# Adafruit_CH334F_Mini_4-Port_USB_Hub_Brea.net
KiCad netlist of a schematic drawn in EAGLE
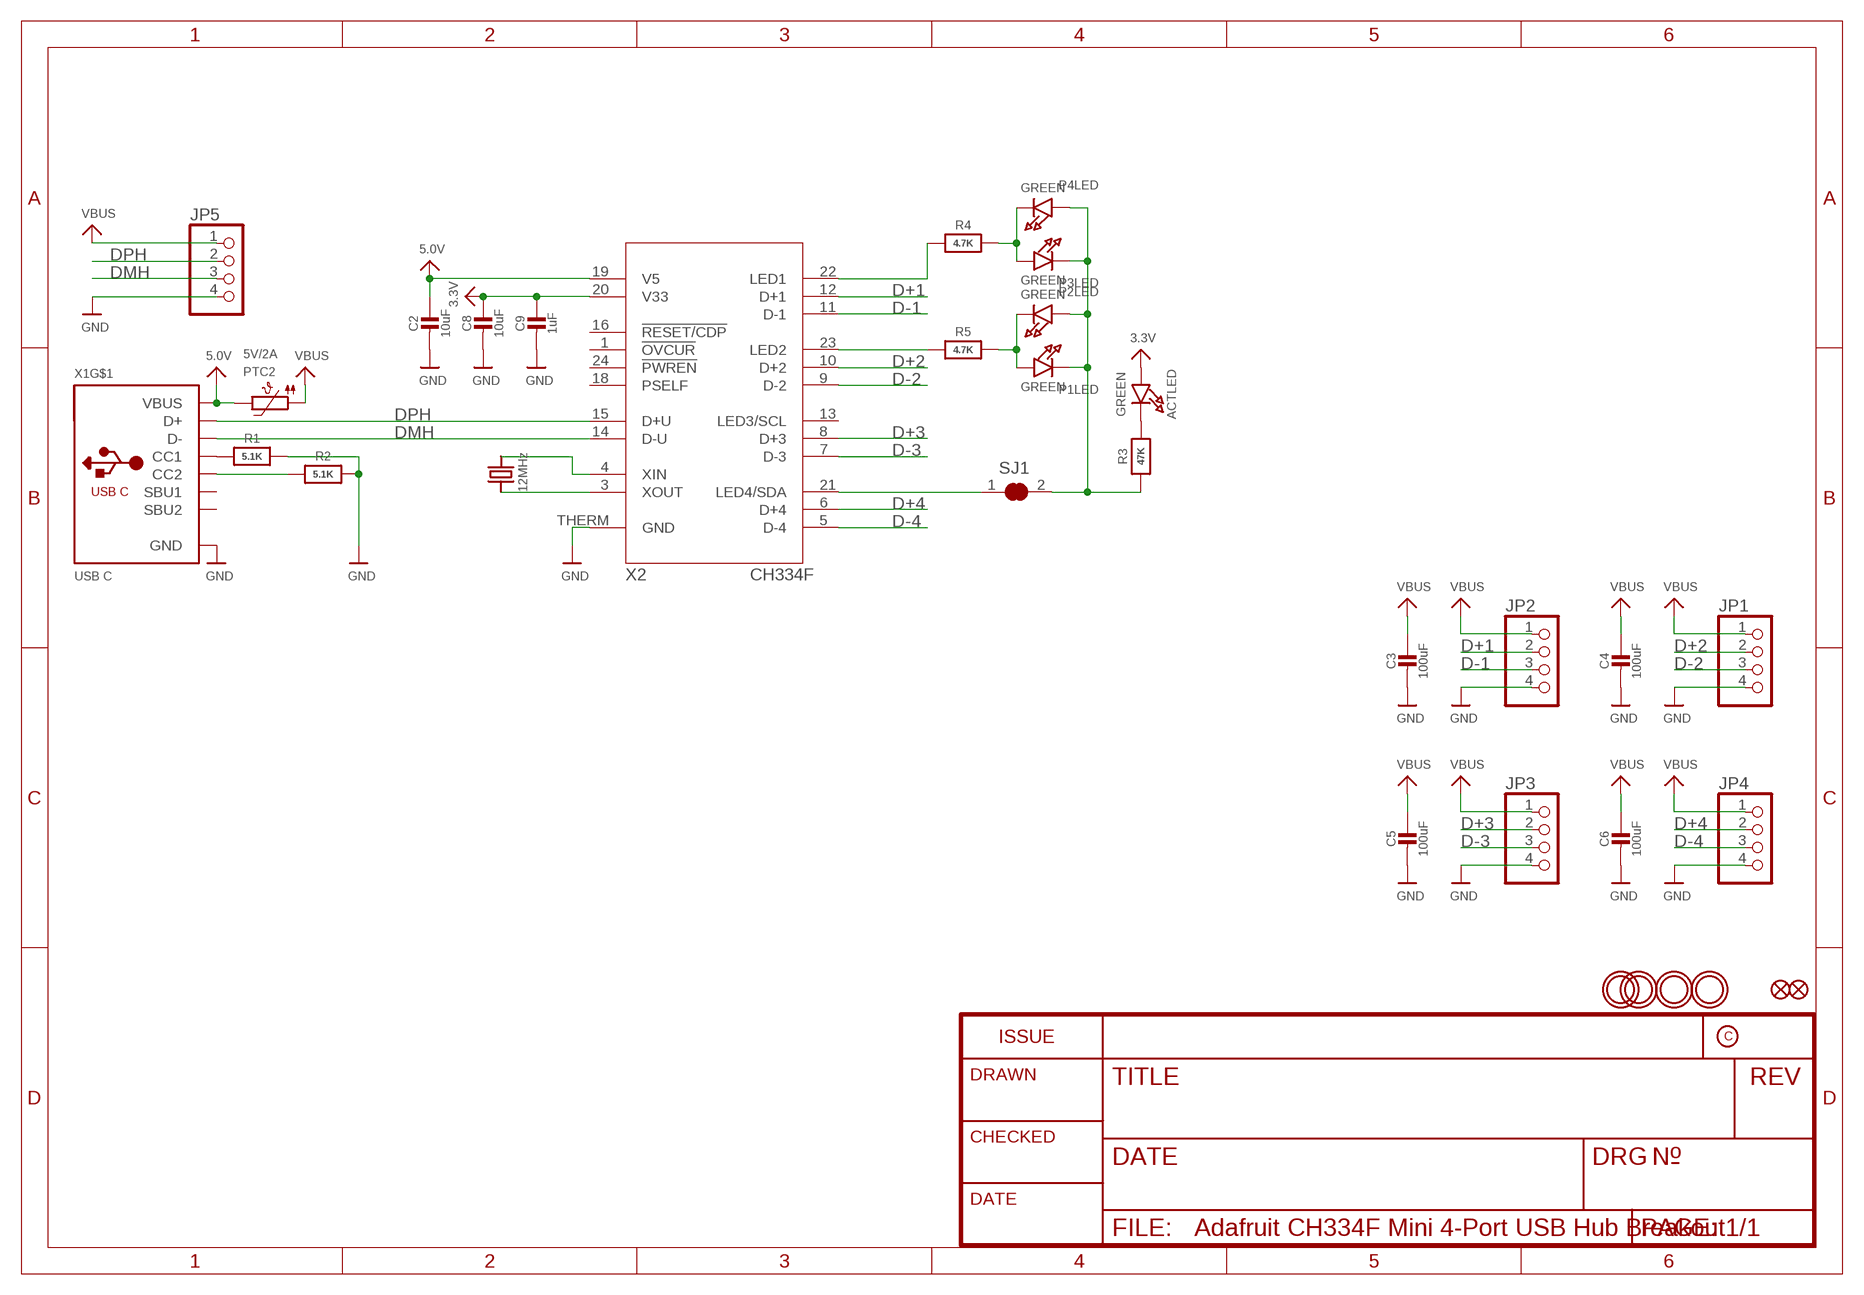
[diagram p0: schematic, sheet 1]

(export (version "E")
  (design (tool "Eeschema 10.0.6"))
  (components
    (comp (ref "ACTLED")
      (value "GREEN")
      (footprint "eagle-import:CHIPLED_0603_NOOUTLINE")
      (libsource (lib "eagle-import") (part "LED0603_NOOUTLINE"))
    )
    (comp (ref "C2")
      (value "10uF")
      (footprint "eagle-import:0805-NO")
      (libsource (lib "eagle-import") (part "CAP_CERAMIC0805-NOOUTLINE"))
    )
    (comp (ref "C3")
      (value "100uF")
      (footprint "eagle-import:_1206")
      (libsource (lib "eagle-import") (part "CAP_CERAMIC_1206"))
    )
    (comp (ref "C4")
      (value "100uF")
      (footprint "eagle-import:_1206")
      (libsource (lib "eagle-import") (part "CAP_CERAMIC_1206"))
    )
    (comp (ref "C5")
      (value "100uF")
      (footprint "eagle-import:_1206")
      (libsource (lib "eagle-import") (part "CAP_CERAMIC_1206"))
    )
    (comp (ref "C6")
      (value "100uF")
      (footprint "eagle-import:_1206")
      (libsource (lib "eagle-import") (part "CAP_CERAMIC_1206"))
    )
    (comp (ref "C8")
      (value "10uF")
      (footprint "eagle-import:0805-NO")
      (libsource (lib "eagle-import") (part "CAP_CERAMIC0805-NOOUTLINE"))
    )
    (comp (ref "C9")
      (value "1uF")
      (footprint "eagle-import:0603-NO")
      (libsource (lib "eagle-import") (part "CAP_CERAMIC0603_NO"))
    )
    (comp (ref "FID1")
      (value "FIDUCIAL_0.5MM")
      (footprint "eagle-import:FIDUCIAL_0.5MM")
      (libsource (lib "eagle-import") (part "FIDUCIAL_0.5MM"))
    )
    (comp (ref "FID2")
      (value "FIDUCIAL_0.5MM")
      (footprint "eagle-import:FIDUCIAL_0.5MM")
      (libsource (lib "eagle-import") (part "FIDUCIAL_0.5MM"))
    )
    (comp (ref "JP1")
      (value "HEADER-1X4ROUND")
      (footprint "eagle-import:1X04_ROUND")
      (libsource (lib "eagle-import") (part "HEADER-1X4ROUND"))
    )
    (comp (ref "JP2")
      (value "HEADER-1X4ROUND")
      (footprint "eagle-import:1X04_ROUND")
      (libsource (lib "eagle-import") (part "HEADER-1X4ROUND"))
    )
    (comp (ref "JP3")
      (value "HEADER-1X4ROUND")
      (footprint "eagle-import:1X04_ROUND")
      (libsource (lib "eagle-import") (part "HEADER-1X4ROUND"))
    )
    (comp (ref "JP4")
      (value "HEADER-1X4ROUND")
      (footprint "eagle-import:1X04_ROUND")
      (libsource (lib "eagle-import") (part "HEADER-1X4ROUND"))
    )
    (comp (ref "JP5")
      (value "HEADER-1X4ROUND")
      (footprint "eagle-import:1X04_ROUND")
      (libsource (lib "eagle-import") (part "HEADER-1X4ROUND"))
    )
    (comp (ref "P1LED")
      (value "GREEN")
      (footprint "eagle-import:CHIPLED_0603_NOOUTLINE")
      (libsource (lib "eagle-import") (part "LED0603_NOOUTLINE"))
    )
    (comp (ref "P2LED")
      (value "GREEN")
      (footprint "eagle-import:CHIPLED_0603_NOOUTLINE")
      (libsource (lib "eagle-import") (part "LED0603_NOOUTLINE"))
    )
    (comp (ref "P3LED")
      (value "GREEN")
      (footprint "eagle-import:CHIPLED_0603_NOOUTLINE")
      (libsource (lib "eagle-import") (part "LED0603_NOOUTLINE"))
    )
    (comp (ref "P4LED")
      (value "GREEN")
      (footprint "eagle-import:CHIPLED_0603_NOOUTLINE")
      (libsource (lib "eagle-import") (part "LED0603_NOOUTLINE"))
    )
    (comp (ref "PTC2")
      (value "5V/2A")
      (footprint "eagle-import:0805-NO")
      (libsource (lib "eagle-import") (part "PTC_0805"))
    )
    (comp (ref "R1")
      (value "5.1K")
      (footprint "eagle-import:0603-NO")
      (libsource (lib "eagle-import") (part "RESISTOR_0603_NOOUT"))
    )
    (comp (ref "R2")
      (value "5.1K")
      (footprint "eagle-import:0603-NO")
      (libsource (lib "eagle-import") (part "RESISTOR_0603_NOOUT"))
    )
    (comp (ref "R3")
      (value "47K")
      (footprint "eagle-import:0603-NO")
      (libsource (lib "eagle-import") (part "RESISTOR_0603_NOOUT"))
    )
    (comp (ref "R4")
      (value "4.7K")
      (footprint "eagle-import:0603-NO")
      (libsource (lib "eagle-import") (part "RESISTOR_0603_NOOUT"))
    )
    (comp (ref "R5")
      (value "4.7K")
      (footprint "eagle-import:0603-NO")
      (libsource (lib "eagle-import") (part "RESISTOR_0603_NOOUT"))
    )
    (comp (ref "SJ1")
      (value "SOLDERJUMPER_CLOSED")
      (footprint "eagle-import:SOLDERJUMPER_CLOSEDWIRE")
      (libsource (lib "eagle-import") (part "SOLDERJUMPER_CLOSED"))
    )
    (comp (ref "U$23")
      (value "MOUNTINGHOLE2.5")
      (footprint "eagle-import:MOUNTINGHOLE_2.5_PLATED")
      (libsource (lib "eagle-import") (part "MOUNTINGHOLE2.5"))
    )
    (comp (ref "U$28")
      (value "MOUNTINGHOLE2.5")
      (footprint "eagle-import:MOUNTINGHOLE_2.5_PLATED")
      (libsource (lib "eagle-import") (part "MOUNTINGHOLE2.5"))
    )
    (comp (ref "U$29")
      (value "MOUNTINGHOLE2.5")
      (footprint "eagle-import:MOUNTINGHOLE_2.5_PLATED")
      (libsource (lib "eagle-import") (part "MOUNTINGHOLE2.5"))
    )
    (comp (ref "U$31")
      (value "MOUNTINGHOLE2.5")
      (footprint "eagle-import:MOUNTINGHOLE_2.5_PLATED")
      (libsource (lib "eagle-import") (part "MOUNTINGHOLE2.5"))
    )
    (comp (ref "X1")
      (value "USB C")
      (footprint "eagle-import:USB_C_CUSB31-CFM2AX-01-X")
      (libsource (lib "eagle-import") (part "USB_C"))
    )
    (comp (ref "X2")
      (value "CH334F")
      (footprint "eagle-import:QFN24_4MM")
      (libsource (lib "eagle-import") (part "CH334F"))
    )
    (comp (ref "Y1")
      (value "12MHz")
      (footprint "eagle-import:CRYSTAL_2.5X2")
      (libsource (lib "eagle-import") (part "CRYSTAL2.5X2.0"))
    )
  )
  (nets
    (net (code "1") (name "/D+1") (class "Default")
      (node (ref "JP2") (pin "2") (pinfunction "2_2") (pintype "passive"))
      (node (ref "X2") (pin "12") (pinfunction "D+1_12") (pintype "bidirectional"))
    )
    (net (code "2") (name "/D+2") (class "Default")
      (node (ref "JP1") (pin "2") (pinfunction "2_2") (pintype "passive"))
      (node (ref "X2") (pin "10") (pinfunction "D+2_10") (pintype "bidirectional"))
    )
    (net (code "3") (name "/D+3") (class "Default")
      (node (ref "JP3") (pin "2") (pinfunction "2_2") (pintype "passive"))
      (node (ref "X2") (pin "8") (pinfunction "D+3_8") (pintype "bidirectional"))
    )
    (net (code "4") (name "/D+4") (class "Default")
      (node (ref "JP4") (pin "2") (pinfunction "2_2") (pintype "passive"))
      (node (ref "X2") (pin "6") (pinfunction "D+4_6") (pintype "bidirectional"))
    )
    (net (code "5") (name "/D-1") (class "Default")
      (node (ref "JP2") (pin "3") (pinfunction "3_3") (pintype "passive"))
      (node (ref "X2") (pin "11") (pinfunction "D-1_11") (pintype "bidirectional"))
    )
    (net (code "6") (name "/D-2") (class "Default")
      (node (ref "JP1") (pin "3") (pinfunction "3_3") (pintype "passive"))
      (node (ref "X2") (pin "9") (pinfunction "D-2_9") (pintype "bidirectional"))
    )
    (net (code "7") (name "/D-3") (class "Default")
      (node (ref "JP3") (pin "3") (pinfunction "3_3") (pintype "passive"))
      (node (ref "X2") (pin "7") (pinfunction "D-3_7") (pintype "bidirectional"))
    )
    (net (code "8") (name "/D-4") (class "Default")
      (node (ref "JP4") (pin "3") (pinfunction "3_3") (pintype "passive"))
      (node (ref "X2") (pin "5") (pinfunction "D-4_5") (pintype "bidirectional"))
    )
    (net (code "9") (name "/DMH") (class "Default")
      (node (ref "JP5") (pin "3") (pinfunction "3_3") (pintype "passive"))
      (node (ref "X1") (pin "A7") (pinfunction "D-_A7") (pintype "bidirectional"))
      (node (ref "X1") (pin "B7") (pinfunction "D-_B7") (pintype "bidirectional"))
      (node (ref "X2") (pin "14") (pinfunction "D-U_14") (pintype "bidirectional"))
    )
    (net (code "10") (name "/DPH") (class "Default")
      (node (ref "JP5") (pin "2") (pinfunction "2_2") (pintype "passive"))
      (node (ref "X1") (pin "A6") (pinfunction "D+_A6") (pintype "bidirectional"))
      (node (ref "X1") (pin "B6") (pinfunction "D+_B6") (pintype "bidirectional"))
      (node (ref "X2") (pin "15") (pinfunction "D+U_15") (pintype "bidirectional"))
    )
    (net (code "11") (name "3.3V") (class "Default")
      (node (ref "ACTLED") (pin "A") (pinfunction "A_A") (pintype "passive"))
      (node (ref "C8") (pin "1") (pinfunction "1_1") (pintype "passive"))
      (node (ref "C9") (pin "1") (pinfunction "1_1") (pintype "passive"))
      (node (ref "X2") (pin "20") (pinfunction "V33_20") (pintype "power_in"))
    )
    (net (code "12") (name "5.0V") (class "Default")
      (node (ref "C2") (pin "1") (pinfunction "1_1") (pintype "passive"))
      (node (ref "PTC2") (pin "2") (pinfunction "2_2") (pintype "passive"))
      (node (ref "X1") (pin "A4B9") (pinfunction "VBUS_A4B9") (pintype "power_in"))
      (node (ref "X1") (pin "B4A9") (pinfunction "VBUS_B4A9") (pintype "power_in"))
      (node (ref "X2") (pin "19") (pinfunction "V5_19") (pintype "power_in"))
    )
    (net (code "13") (name "GND") (class "Default")
      (node (ref "C2") (pin "2") (pinfunction "2_2") (pintype "passive"))
      (node (ref "C3") (pin "2") (pinfunction "2_2") (pintype "passive"))
      (node (ref "C4") (pin "2") (pinfunction "2_2") (pintype "passive"))
      (node (ref "C5") (pin "2") (pinfunction "2_2") (pintype "passive"))
      (node (ref "C6") (pin "2") (pinfunction "2_2") (pintype "passive"))
      (node (ref "C8") (pin "2") (pinfunction "2_2") (pintype "passive"))
      (node (ref "C9") (pin "2") (pinfunction "2_2") (pintype "passive"))
      (node (ref "JP1") (pin "4") (pinfunction "4_4") (pintype "passive"))
      (node (ref "JP2") (pin "4") (pinfunction "4_4") (pintype "passive"))
      (node (ref "JP3") (pin "4") (pinfunction "4_4") (pintype "passive"))
      (node (ref "JP4") (pin "4") (pinfunction "4_4") (pintype "passive"))
      (node (ref "JP5") (pin "4") (pinfunction "4_4") (pintype "passive"))
      (node (ref "R1") (pin "2") (pinfunction "2_2") (pintype "passive"))
      (node (ref "R2") (pin "2") (pinfunction "2_2") (pintype "passive"))
      (node (ref "X1") (pin "A1B12") (pinfunction "GND_A1B12") (pintype "power_in"))
      (node (ref "X1") (pin "B1A12") (pinfunction "GND_B1A12") (pintype "power_in"))
      (node (ref "X2") (pin "THERM") (pinfunction "GND_THERM") (pintype "power_in"))
    )
    (net (code "14") (name "Net-(ACTLED-PadC)") (class "Default")
      (node (ref "ACTLED") (pin "C") (pinfunction "C_C") (pintype "passive"))
      (node (ref "R3") (pin "2") (pinfunction "2_2") (pintype "passive"))
    )
    (net (code "15") (name "Net-(P1LED-PadA)") (class "Default")
      (node (ref "P1LED") (pin "A") (pinfunction "A_A") (pintype "passive"))
      (node (ref "P2LED") (pin "C") (pinfunction "C_C") (pintype "passive"))
      (node (ref "R5") (pin "2") (pinfunction "2_2") (pintype "passive"))
    )
    (net (code "16") (name "Net-(P1LED-PadC)") (class "Default")
      (node (ref "P1LED") (pin "C") (pinfunction "C_C") (pintype "passive"))
      (node (ref "P2LED") (pin "A") (pinfunction "A_A") (pintype "passive"))
      (node (ref "P3LED") (pin "C") (pinfunction "C_C") (pintype "passive"))
      (node (ref "P4LED") (pin "A") (pinfunction "A_A") (pintype "passive"))
      (node (ref "R3") (pin "1") (pinfunction "1_1") (pintype "passive"))
      (node (ref "SJ1") (pin "2") (pinfunction "2_2") (pintype "passive"))
    )
    (net (code "17") (name "Net-(P3LED-PadA)") (class "Default")
      (node (ref "P3LED") (pin "A") (pinfunction "A_A") (pintype "passive"))
      (node (ref "P4LED") (pin "C") (pinfunction "C_C") (pintype "passive"))
      (node (ref "R4") (pin "2") (pinfunction "2_2") (pintype "passive"))
    )
    (net (code "18") (name "Net-(X1A-CC1)") (class "Default")
      (node (ref "R1") (pin "1") (pinfunction "1_1") (pintype "passive"))
      (node (ref "X1") (pin "A5") (pinfunction "CC1_A5") (pintype "bidirectional"))
    )
    (net (code "19") (name "Net-(X1A-CC2)") (class "Default")
      (node (ref "R2") (pin "1") (pinfunction "1_1") (pintype "passive"))
      (node (ref "X1") (pin "B5") (pinfunction "CC2_B5") (pintype "bidirectional"))
    )
    (net (code "20") (name "Net-(X2-LED1)") (class "Default")
      (node (ref "R4") (pin "1") (pinfunction "1_1") (pintype "passive"))
      (node (ref "X2") (pin "22") (pinfunction "LED1_22") (pintype "bidirectional"))
    )
    (net (code "21") (name "Net-(X2-LED2)") (class "Default")
      (node (ref "R5") (pin "1") (pinfunction "1_1") (pintype "passive"))
      (node (ref "X2") (pin "23") (pinfunction "LED2_23") (pintype "bidirectional"))
    )
    (net (code "22") (name "Net-(X2-LED4{slash}SDA)") (class "Default")
      (node (ref "SJ1") (pin "1") (pinfunction "1_1") (pintype "passive"))
      (node (ref "X2") (pin "21") (pinfunction "LED4/SDA_21") (pintype "bidirectional"))
    )
    (net (code "23") (name "Net-(X2-XIN)") (class "Default")
      (node (ref "X2") (pin "4") (pinfunction "XIN_4") (pintype "input"))
      (node (ref "Y1") (pin "3") (pinfunction "2_3") (pintype "passive"))
    )
    (net (code "24") (name "Net-(X2-XOUT)") (class "Default")
      (node (ref "X2") (pin "3") (pinfunction "XOUT_3") (pintype "output"))
      (node (ref "Y1") (pin "1") (pinfunction "1_1") (pintype "passive"))
    )
    (net (code "25") (name "VBUS") (class "Default")
      (node (ref "C3") (pin "1") (pinfunction "1_1") (pintype "passive"))
      (node (ref "C4") (pin "1") (pinfunction "1_1") (pintype "passive"))
      (node (ref "C5") (pin "1") (pinfunction "1_1") (pintype "passive"))
      (node (ref "C6") (pin "1") (pinfunction "1_1") (pintype "passive"))
      (node (ref "JP1") (pin "1") (pinfunction "1_1") (pintype "passive"))
      (node (ref "JP2") (pin "1") (pinfunction "1_1") (pintype "passive"))
      (node (ref "JP3") (pin "1") (pinfunction "1_1") (pintype "passive"))
      (node (ref "JP4") (pin "1") (pinfunction "1_1") (pintype "passive"))
      (node (ref "JP5") (pin "1") (pinfunction "1_1") (pintype "passive"))
      (node (ref "PTC2") (pin "1") (pinfunction "1_1") (pintype "passive"))
    )
    (net (code "26") (name "unconnected-(X1A-SBU1-PadA8)") (class "Default")
      (node (ref "X1") (pin "A8") (pinfunction "SBU1_A8") (pintype "bidirectional"))
    )
    (net (code "27") (name "unconnected-(X1A-SBU2-PadB8)") (class "Default")
      (node (ref "X1") (pin "B8") (pinfunction "SBU2_B8") (pintype "bidirectional"))
    )
    (net (code "28") (name "unconnected-(X2-LED3{slash}SCL-Pad13)") (class "Default")
      (node (ref "X2") (pin "13") (pinfunction "LED3/SCL_13") (pintype "bidirectional"))
    )
    (net (code "29") (name "unconnected-(X2-PSELF-Pad18)") (class "Default")
      (node (ref "X2") (pin "18") (pinfunction "PSELF_18") (pintype "input"))
    )
    (net (code "30") (name "unconnected-(X2-~{OVCUR}-Pad1)") (class "Default")
      (node (ref "X2") (pin "1") (pinfunction "~{OVCUR}_1") (pintype "input"))
    )
    (net (code "31") (name "unconnected-(X2-~{PWREN}-Pad24)") (class "Default")
      (node (ref "X2") (pin "24") (pinfunction "~{PWREN}_24") (pintype "output"))
    )
    (net (code "32") (name "unconnected-(X2-~{RESET{slash}CDP}-Pad16)") (class "Default")
      (node (ref "X2") (pin "16") (pinfunction "~{RESET/CDP}_16") (pintype "input"))
    )
  )
)
